# OV7670s.net
KiCad netlist of a schematic drawn in Altium Designer
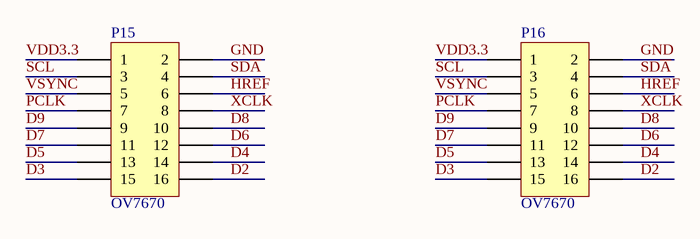
[diagram p0: OV7670s.SchDoc]

(export (version "E")
  (design (tool "Eeschema 10.0.6"))
  (components
    (comp (ref "P15")
      (value "OV7670")
      (footprint "HDR2X8")
      (description "Header, 8-Pin, Dual row")
      (fields (field (name "PUBLISHER") "Altium Limited"))
      (libsource (lib "Miscellaneous Connectors") (part "Header 8X2"))
    )
    (comp (ref "P16")
      (value "OV7670")
      (footprint "HDR2X8")
      (description "Header, 8-Pin, Dual row")
      (fields (field (name "PUBLISHER") "Altium Limited"))
      (libsource (lib "Miscellaneous Connectors") (part "Header 8X2"))
    )
  )
  (nets
    (net (code "1") (name "/D2") (class "Default")
      (node (ref "P15") (pin "16") (pinfunction "16_16") (pintype "passive"))
      (node (ref "P16") (pin "16") (pinfunction "16_16") (pintype "passive"))
    )
    (net (code "2") (name "/D3") (class "Default")
      (node (ref "P15") (pin "15") (pinfunction "15_15") (pintype "passive"))
      (node (ref "P16") (pin "15") (pinfunction "15_15") (pintype "passive"))
    )
    (net (code "3") (name "/D4") (class "Default")
      (node (ref "P15") (pin "14") (pinfunction "14_14") (pintype "passive"))
      (node (ref "P16") (pin "14") (pinfunction "14_14") (pintype "passive"))
    )
    (net (code "4") (name "/D5") (class "Default")
      (node (ref "P15") (pin "13") (pinfunction "13_13") (pintype "passive"))
      (node (ref "P16") (pin "13") (pinfunction "13_13") (pintype "passive"))
    )
    (net (code "5") (name "/D6") (class "Default")
      (node (ref "P15") (pin "12") (pinfunction "12_12") (pintype "passive"))
      (node (ref "P16") (pin "12") (pinfunction "12_12") (pintype "passive"))
    )
    (net (code "6") (name "/D7") (class "Default")
      (node (ref "P15") (pin "11") (pinfunction "11_11") (pintype "passive"))
      (node (ref "P16") (pin "11") (pinfunction "11_11") (pintype "passive"))
    )
    (net (code "7") (name "/D8") (class "Default")
      (node (ref "P15") (pin "10") (pinfunction "10_10") (pintype "passive"))
      (node (ref "P16") (pin "10") (pinfunction "10_10") (pintype "passive"))
    )
    (net (code "8") (name "/D9") (class "Default")
      (node (ref "P15") (pin "9") (pinfunction "9_9") (pintype "passive"))
      (node (ref "P16") (pin "9") (pinfunction "9_9") (pintype "passive"))
    )
    (net (code "9") (name "/GND") (class "Default")
      (node (ref "P15") (pin "2") (pinfunction "2_2") (pintype "passive"))
      (node (ref "P16") (pin "2") (pinfunction "2_2") (pintype "passive"))
    )
    (net (code "10") (name "/HREF") (class "Default")
      (node (ref "P15") (pin "6") (pinfunction "6_6") (pintype "passive"))
      (node (ref "P16") (pin "6") (pinfunction "6_6") (pintype "passive"))
    )
    (net (code "11") (name "/PCLK") (class "Default")
      (node (ref "P15") (pin "7") (pinfunction "7_7") (pintype "passive"))
      (node (ref "P16") (pin "7") (pinfunction "7_7") (pintype "passive"))
    )
    (net (code "12") (name "/SCL") (class "Default")
      (node (ref "P15") (pin "3") (pinfunction "3_3") (pintype "passive"))
      (node (ref "P16") (pin "3") (pinfunction "3_3") (pintype "passive"))
    )
    (net (code "13") (name "/SD~{A}") (class "Default")
      (node (ref "P15") (pin "4") (pinfunction "4_4") (pintype "passive"))
      (node (ref "P16") (pin "4") (pinfunction "4_4") (pintype "passive"))
    )
    (net (code "14") (name "/VDD3.3") (class "Default")
      (node (ref "P15") (pin "1") (pinfunction "1_1") (pintype "passive"))
      (node (ref "P16") (pin "1") (pinfunction "1_1") (pintype "passive"))
    )
    (net (code "15") (name "/VSYNC") (class "Default")
      (node (ref "P15") (pin "5") (pinfunction "5_5") (pintype "passive"))
      (node (ref "P16") (pin "5") (pinfunction "5_5") (pintype "passive"))
    )
    (net (code "16") (name "/XCLK") (class "Default")
      (node (ref "P15") (pin "8") (pinfunction "8_8") (pintype "passive"))
      (node (ref "P16") (pin "8") (pinfunction "8_8") (pintype "passive"))
    )
  )
)
